# led_simple_breakout.net
KiCad netlist of a schematic drawn in EAGLE
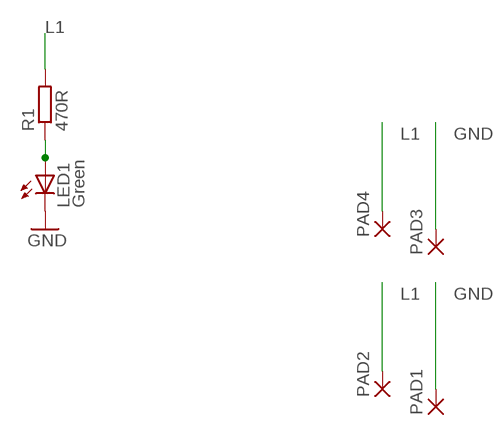
[diagram p0: schematic, sheet 1]

(export (version "E")
  (design (tool "Eeschema 10.0.6"))
  (components
    (comp (ref "LED1")
      (value "Green")
      (footprint "eagle-import:CHIPLED_1206")
      (libsource (lib "eagle-import") (part "LEDCHIPLED_1206"))
    )
    (comp (ref "PAD1")
      (value "SMD2")
      (footprint "eagle-import:SMD1,27-2,54")
      (libsource (lib "eagle-import") (part "SMD2"))
    )
    (comp (ref "PAD2")
      (value "SMD2")
      (footprint "eagle-import:SMD1,27-2,54")
      (libsource (lib "eagle-import") (part "SMD2"))
    )
    (comp (ref "PAD3")
      (value "SMD2")
      (footprint "eagle-import:SMD1,27-2,54")
      (libsource (lib "eagle-import") (part "SMD2"))
    )
    (comp (ref "PAD4")
      (value "SMD2")
      (footprint "eagle-import:SMD1,27-2,54")
      (libsource (lib "eagle-import") (part "SMD2"))
    )
    (comp (ref "R1")
      (value "470R")
      (footprint "eagle-import:R0805")
      (libsource (lib "eagle-import") (part "R-EU_R0805"))
    )
  )
  (nets
    (net (code "1") (name "/L1") (class "Default")
      (node (ref "PAD2") (pin "1") (pinfunction "P_1") (pintype "passive"))
      (node (ref "PAD4") (pin "1") (pinfunction "P_1") (pintype "passive"))
      (node (ref "R1") (pin "2") (pinfunction "2_2") (pintype "passive"))
    )
    (net (code "2") (name "GND") (class "Default")
      (node (ref "LED1") (pin "C") (pinfunction "C_C") (pintype "passive"))
      (node (ref "PAD1") (pin "1") (pinfunction "P_1") (pintype "passive"))
      (node (ref "PAD3") (pin "1") (pinfunction "P_1") (pintype "passive"))
    )
    (net (code "3") (name "Net-(LED1-PadA)") (class "Default")
      (node (ref "LED1") (pin "A") (pinfunction "A_A") (pintype "passive"))
      (node (ref "R1") (pin "1") (pinfunction "1_1") (pintype "passive"))
    )
  )
)
